# Connector.net
KiCad netlist of a schematic drawn in Altium Designer
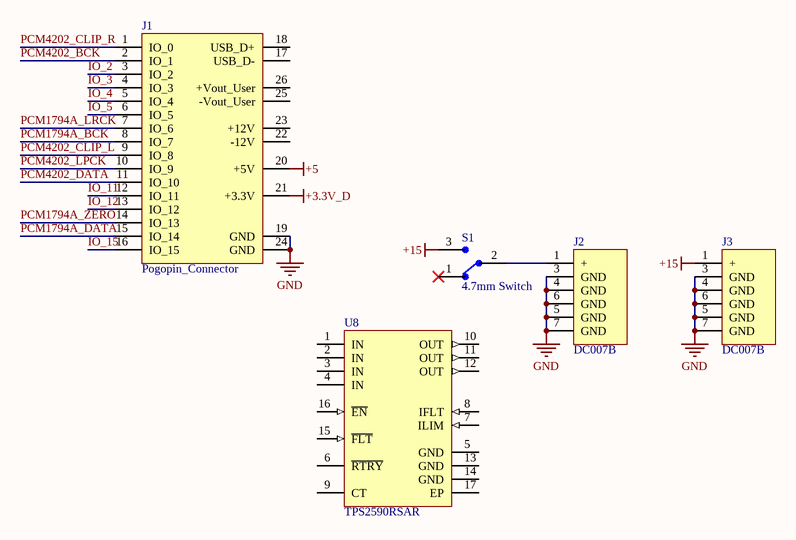
[diagram p0: Connector.SchDoc]

(export (version "E")
  (design (tool "Eeschema 10.0.6"))
  (components
    (comp (ref "J1")
      (value "Pogopin_Connector")
      (footprint "26P_Pogopin")
      (description "Pogopin connector suits Raindrop-S")
      (libsource (lib "Pogopin_Connector") (part "Pogopin_Connector"))
    )
    (comp (ref "J2")
      (value "DC007B")
      (footprint "CONN2_ADC-096-2-T/R_ADM")
      (description "5521")
      (fields
        (field (name "MANUFACTURER_PART_NUMBER") "ADC-096-2-T/R")
        (field (name "COPYRIGHT") "Copyright (C) 2022 Ultra Librarian. All rights reserved.")
      )
      (libsource (lib "DC007B") (part "DC007B"))
    )
    (comp (ref "J3")
      (value "DC007B")
      (footprint "CONN2_ADC-096-2-T/R_ADM")
      (description "5521")
      (fields
        (field (name "MANUFACTURER_PART_NUMBER") "ADC-096-2-T/R")
        (field (name "COPYRIGHT") "Copyright (C) 2022 Ultra Librarian. All rights reserved.")
      )
      (libsource (lib "DC007B") (part "DC007B"))
    )
    (comp (ref "S1")
      (value "4.7mm Switch")
      (footprint "SW_1101M2S3CQE2")
      (description "Slide Switch SPDT Through Hole")
      (fields (field (name "MP") "1101M2S3CQE2") (field (name "DIGI-KEY_PART_NUMBER") "CKN5001-ND"))
      (libsource (lib "Power_Switch") (part "4.7mm Switch"))
    )
    (comp (ref "U8")
      (value "TPS2590RSAR")
      (footprint "FP-RSA0016B-MFG")
      (description "IC HOT SWAP CTRLR GP 16QFN")
      (libsource (lib "TPS2590") (part "CMP-0334-00005-3"))
    )
  )
  (nets
    (net (code "1") (name "+3.3V_D") (class "Default")
      (node (ref "J1") (pin "21") (pinfunction "+3.3V_21") (pintype "passive"))
    )
    (net (code "2") (name "+5") (class "Default")
      (node (ref "J1") (pin "20") (pinfunction "+5V_20") (pintype "passive"))
    )
    (net (code "3") (name "+15") (class "Default")
      (node (ref "J3") (pin "1") (pinfunction "+_1") (pintype "passive"))
      (node (ref "S1") (pin "3") (pinfunction "3_3") (pintype "passive"))
    )
    (net (code "4") (name "/IO_2") (class "Default")
      (node (ref "J1") (pin "3") (pinfunction "IO_2_3") (pintype "passive"))
    )
    (net (code "5") (name "/IO_3") (class "Default")
      (node (ref "J1") (pin "4") (pinfunction "IO_3_4") (pintype "passive"))
    )
    (net (code "6") (name "/IO_4") (class "Default")
      (node (ref "J1") (pin "5") (pinfunction "IO_4_5") (pintype "passive"))
    )
    (net (code "7") (name "/IO_5") (class "Default")
      (node (ref "J1") (pin "6") (pinfunction "IO_5_6") (pintype "passive"))
    )
    (net (code "8") (name "/IO_11") (class "Default")
      (node (ref "J1") (pin "12") (pinfunction "IO_11_12") (pintype "passive"))
    )
    (net (code "9") (name "/IO_12") (class "Default")
      (node (ref "J1") (pin "13") (pinfunction "IO_12_13") (pintype "passive"))
    )
    (net (code "10") (name "/IO_15") (class "Default")
      (node (ref "J1") (pin "16") (pinfunction "IO_15_16") (pintype "passive"))
    )
    (net (code "11") (name "/PCM1794A_BCK") (class "Default")
      (node (ref "J1") (pin "8") (pinfunction "IO_7_8") (pintype "passive"))
    )
    (net (code "12") (name "/PCM1794A_DATA") (class "Default")
      (node (ref "J1") (pin "15") (pinfunction "IO_14_15") (pintype "passive"))
    )
    (net (code "13") (name "/PCM1794A_LRCK") (class "Default")
      (node (ref "J1") (pin "7") (pinfunction "IO_6_7") (pintype "passive"))
    )
    (net (code "14") (name "/PCM1794A_ZERO") (class "Default")
      (node (ref "J1") (pin "14") (pinfunction "IO_13_14") (pintype "passive"))
    )
    (net (code "15") (name "/PCM4202_BCK") (class "Default")
      (node (ref "J1") (pin "2") (pinfunction "IO_1_2") (pintype "passive"))
    )
    (net (code "16") (name "/PCM4202_CLIP_L") (class "Default")
      (node (ref "J1") (pin "9") (pinfunction "IO_8_9") (pintype "passive"))
    )
    (net (code "17") (name "/PCM4202_CLIP_R") (class "Default")
      (node (ref "J1") (pin "1") (pinfunction "IO_0_1") (pintype "passive"))
    )
    (net (code "18") (name "/PCM4202_DATA") (class "Default")
      (node (ref "J1") (pin "11") (pinfunction "IO_10_11") (pintype "passive"))
    )
    (net (code "19") (name "/PCM4202_LPCK") (class "Default")
      (node (ref "J1") (pin "10") (pinfunction "IO_9_10") (pintype "passive"))
    )
    (net (code "20") (name "GND") (class "Default")
      (node (ref "J1") (pin "19") (pinfunction "GND_19") (pintype "passive"))
      (node (ref "J1") (pin "24") (pinfunction "GND_24") (pintype "passive"))
      (node (ref "J2") (pin "3") (pinfunction "GND_3") (pintype "passive"))
      (node (ref "J2") (pin "4") (pinfunction "GND_4") (pintype "passive"))
      (node (ref "J2") (pin "5") (pinfunction "GND_5") (pintype "passive"))
      (node (ref "J2") (pin "6") (pinfunction "GND_6") (pintype "passive"))
      (node (ref "J2") (pin "7") (pinfunction "GND_7") (pintype "passive"))
      (node (ref "J3") (pin "3") (pinfunction "GND_3") (pintype "passive"))
      (node (ref "J3") (pin "4") (pinfunction "GND_4") (pintype "passive"))
      (node (ref "J3") (pin "5") (pinfunction "GND_5") (pintype "passive"))
      (node (ref "J3") (pin "6") (pinfunction "GND_6") (pintype "passive"))
      (node (ref "J3") (pin "7") (pinfunction "GND_7") (pintype "passive"))
    )
    (net (code "21") (name "Net-(J2-+)") (class "Default")
      (node (ref "J2") (pin "1") (pinfunction "+_1") (pintype "passive"))
      (node (ref "S1") (pin "2") (pinfunction "2_2") (pintype "passive"))
    )
    (net (code "22") (name "unconnected-(J1-+12V-Pad23)") (class "Default")
      (node (ref "J1") (pin "23") (pinfunction "+12V_23") (pintype "passive"))
    )
    (net (code "23") (name "unconnected-(J1-+Vout_User-Pad26)") (class "Default")
      (node (ref "J1") (pin "26") (pinfunction "+Vout_User_26") (pintype "passive"))
    )
    (net (code "24") (name "unconnected-(J1--12V-Pad22)") (class "Default")
      (node (ref "J1") (pin "22") (pinfunction "-12V_22") (pintype "passive"))
    )
    (net (code "25") (name "unconnected-(J1--Vout_User-Pad25)") (class "Default")
      (node (ref "J1") (pin "25") (pinfunction "-Vout_User_25") (pintype "passive"))
    )
    (net (code "26") (name "unconnected-(J1-USB_D+-Pad18)") (class "Default")
      (node (ref "J1") (pin "18") (pinfunction "USB_D+_18") (pintype "passive"))
    )
    (net (code "27") (name "unconnected-(J1-USB_D--Pad17)") (class "Default")
      (node (ref "J1") (pin "17") (pinfunction "USB_D-_17") (pintype "passive"))
    )
    (net (code "28") (name "unconnected-(S1-Pad1)") (class "Default")
      (node (ref "S1") (pin "1") (pinfunction "1_1") (pintype "passive+no_connect"))
    )
    (net (code "29") (name "unconnected-(U8-CT-Pad9)") (class "Default")
      (node (ref "U8") (pin "9") (pinfunction "CT_9") (pintype "passive"))
    )
    (net (code "30") (name "unconnected-(U8-EP-Pad17)") (class "Default")
      (node (ref "U8") (pin "17") (pinfunction "EP_17") (pintype "power_in"))
    )
    (net (code "31") (name "unconnected-(U8-GND-Pad5)") (class "Default")
      (node (ref "U8") (pin "5") (pinfunction "GND_5") (pintype "power_in"))
    )
    (net (code "32") (name "unconnected-(U8-GND-Pad13)") (class "Default")
      (node (ref "U8") (pin "13") (pinfunction "GND_13") (pintype "power_in"))
    )
    (net (code "33") (name "unconnected-(U8-GND-Pad14)") (class "Default")
      (node (ref "U8") (pin "14") (pinfunction "GND_14") (pintype "power_in"))
    )
    (net (code "34") (name "unconnected-(U8-IFLT-Pad8)") (class "Default")
      (node (ref "U8") (pin "8") (pinfunction "IFLT_8") (pintype "input"))
    )
    (net (code "35") (name "unconnected-(U8-ILIM-Pad7)") (class "Default")
      (node (ref "U8") (pin "7") (pinfunction "ILIM_7") (pintype "input"))
    )
    (net (code "36") (name "unconnected-(U8-IN-Pad1)") (class "Default")
      (node (ref "U8") (pin "1") (pinfunction "IN_1") (pintype "power_in"))
    )
    (net (code "37") (name "unconnected-(U8-IN-Pad2)") (class "Default")
      (node (ref "U8") (pin "2") (pinfunction "IN_2") (pintype "power_in"))
    )
    (net (code "38") (name "unconnected-(U8-IN-Pad3)") (class "Default")
      (node (ref "U8") (pin "3") (pinfunction "IN_3") (pintype "power_in"))
    )
    (net (code "39") (name "unconnected-(U8-IN-Pad4)") (class "Default")
      (node (ref "U8") (pin "4") (pinfunction "IN_4") (pintype "power_in"))
    )
    (net (code "40") (name "unconnected-(U8-OUT-Pad10)") (class "Default")
      (node (ref "U8") (pin "10") (pinfunction "OUT_10") (pintype "output"))
    )
    (net (code "41") (name "unconnected-(U8-OUT-Pad11)") (class "Default")
      (node (ref "U8") (pin "11") (pinfunction "OUT_11") (pintype "output"))
    )
    (net (code "42") (name "unconnected-(U8-OUT-Pad12)") (class "Default")
      (node (ref "U8") (pin "12") (pinfunction "OUT_12") (pintype "output"))
    )
    (net (code "43") (name "unconnected-(U8-~{EN}-Pad16)") (class "Default")
      (node (ref "U8") (pin "16") (pinfunction "~{EN}_16") (pintype "input"))
    )
    (net (code "44") (name "unconnected-(U8-~{FLT}-Pad15)") (class "Default")
      (node (ref "U8") (pin "15") (pinfunction "~{FLT}_15") (pintype "input"))
    )
    (net (code "45") (name "unconnected-(U8-~{RTRY}-Pad6)") (class "Default")
      (node (ref "U8") (pin "6") (pinfunction "~{RTRY}_6") (pintype "passive"))
    )
  )
)
